# 1_power.net
KiCad netlist of a schematic drawn in Altium Designer
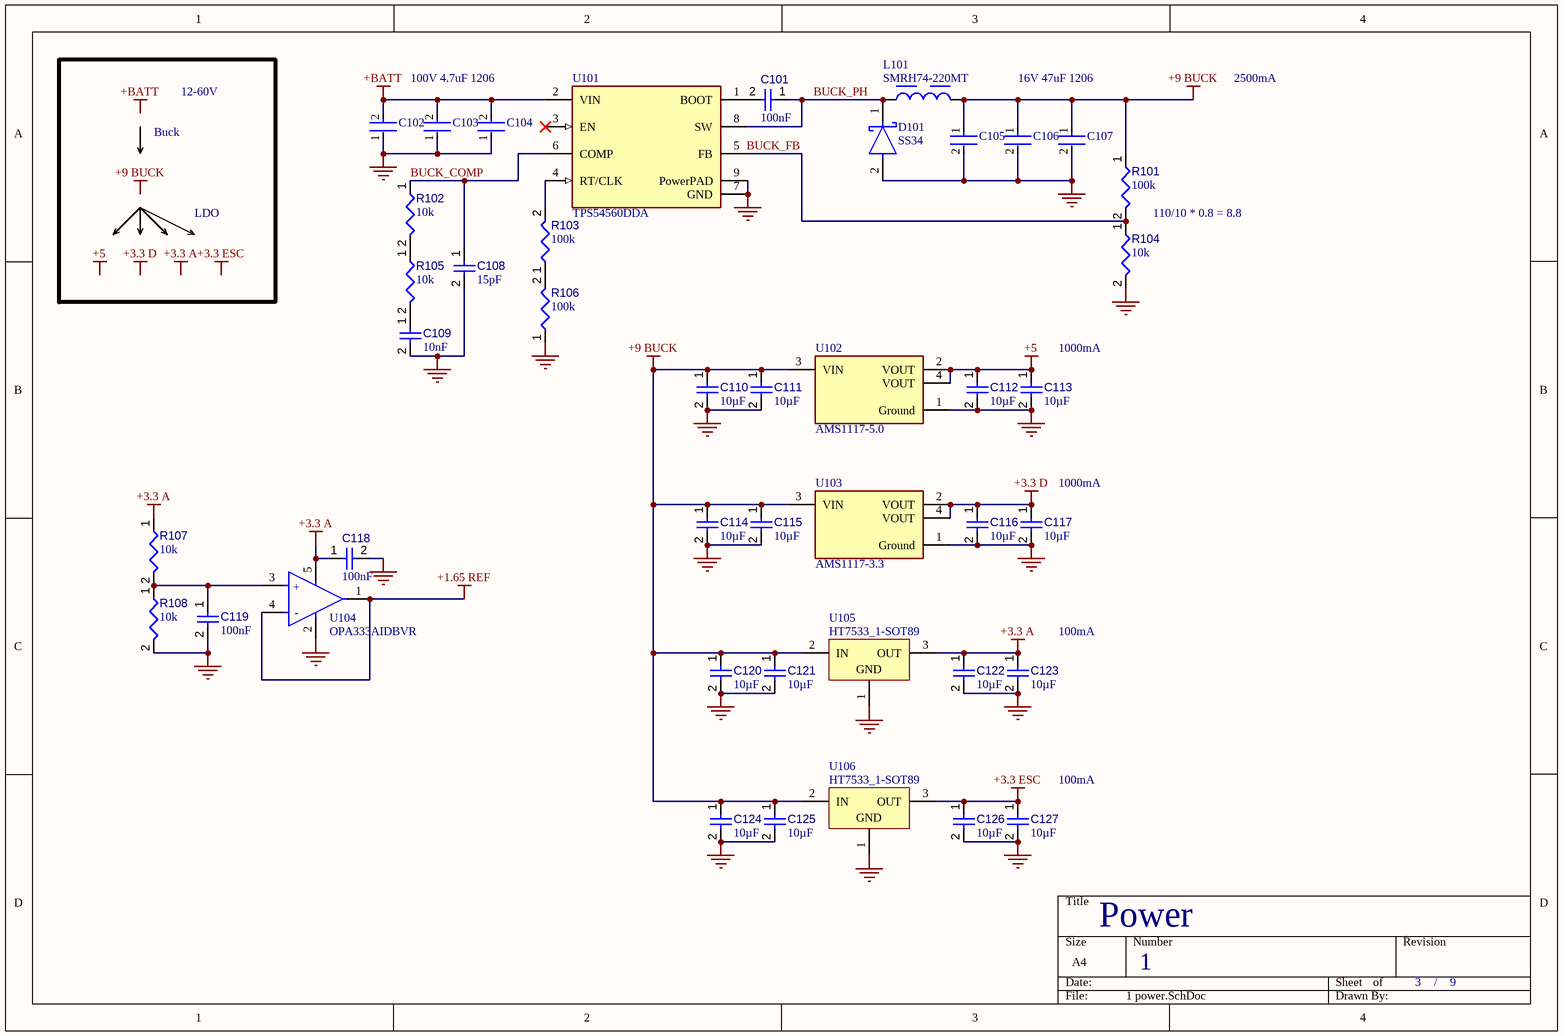
[diagram p0: 1 power.SchDoc]

(export (version "E")
  (design (tool "Eeschema 10.0.6"))
  (components
    (comp (ref "C101")
      (value "100nF")
      (footprint "CAPC0402(1005)60_L")
      (description "Chip Capacitor, 100nF +/-20%, 25V, 0402, Thickness 0.6 mm")
      (fields (field (name "TOLERANCE") "10%") (field (name "Comment") "Capacitor 100nF +/-20% 25V 0402"))
      (libsource (lib "UBC Uncrewed Aircraft Systems") (part "CAP-NP-2"))
    )
    (comp (ref "C102")
      (value "GRM31CZ72A475KE11L")
      (footprint "FP-GRM31C-0_3-e0_3_0_9-MFG")
      (description "Chip Multilayer Ceramic Capacitors for General Purpose, 1206, 4.7uF, X7R, 15%, 10%, 100V")
      (libsource (lib "Altium Content Vault") (part "f23184f103b6ebe33a8c269c53dcba6"))
    )
    (comp (ref "C103")
      (value "GRM31CZ72A475KE11L")
      (footprint "FP-GRM31C-0_3-e0_3_0_9-MFG")
      (description "Chip Multilayer Ceramic Capacitors for General Purpose, 1206, 4.7uF, X7R, 15%, 10%, 100V")
      (libsource (lib "Altium Content Vault") (part "f23184f103b6ebe33a8c269c53dcba6"))
    )
    (comp (ref "C104")
      (value "GRM31CZ72A475KE11L")
      (footprint "FP-GRM31C-0_3-e0_3_0_9-MFG")
      (description "Chip Multilayer Ceramic Capacitors for General Purpose, 1206, 4.7uF, X7R, 15%, 10%, 100V")
      (libsource (lib "Altium Content Vault") (part "f23184f103b6ebe33a8c269c53dcba6"))
    )
    (comp (ref "C105")
      (value "C3216X5R1C476M160AB")
      (footprint "FP-C3216-160-0_2-MFG")
      (description "Multilayer Ceramic Capacitors 47uF ±20% 16V X5R SMD 1206")
      (fields (field (name "TOLERANCE") "20%"))
      (libsource (lib "Altium Content Vault") (part "11868f565c42a9108669ba33697ecf6"))
    )
    (comp (ref "C106")
      (value "C3216X5R1C476M160AB")
      (footprint "FP-C3216-160-0_2-MFG")
      (description "Multilayer Ceramic Capacitors 47uF ±20% 16V X5R SMD 1206")
      (fields (field (name "TOLERANCE") "20%"))
      (libsource (lib "Altium Content Vault") (part "11868f565c42a9108669ba33697ecf6"))
    )
    (comp (ref "C107")
      (value "C3216X5R1C476M160AB")
      (footprint "FP-C3216-160-0_2-MFG")
      (description "Multilayer Ceramic Capacitors 47uF ±20% 16V X5R SMD 1206")
      (fields (field (name "TOLERANCE") "20%"))
      (libsource (lib "Altium Content Vault") (part "11868f565c42a9108669ba33697ecf6"))
    )
    (comp (ref "C108")
      (value "15pF")
      (footprint "CAPC0402(1005)60_L")
      (description "Chip Capacitor, 15pF +/-20%, 50V, 0402, Thickness 0.6 mm")
      (fields (field (name "TOLERANCE") "5%") (field (name "JLCPCB PART #") "C1548"))
      (libsource (lib "UBC Uncrewed Aircraft Systems") (part "CAP-NP-2"))
    )
    (comp (ref "C109")
      (value "10nF")
      (footprint "CAPC0402(1005)60_L")
      (description "Chip Capacitor, 10nF +/-20%, 50V, 0402, Thickness 0.6 mm")
      (fields (field (name "TOLERANCE") "5%") (field (name "JLCPCB PART #") "C15195"))
      (libsource (lib "UBC Uncrewed Aircraft Systems") (part "CAP-NP-2"))
    )
    (comp (ref "C110")
      (value "10µF")
      (footprint "CAPC0603(1608)100_L")
      (description "Chip Capacitor, 10µF +/-20%, 10V, 0603, Thickness 1 mm")
      (fields (field (name "TOLERANCE") "10%") (field (name "Comment") "Capacitor 10µF +/-20% 10V 0603"))
      (libsource (lib "UBC Uncrewed Aircraft Systems") (part "CAP-NP-2"))
    )
    (comp (ref "C111")
      (value "10µF")
      (footprint "CAPC0603(1608)100_L")
      (description "Chip Capacitor, 10µF +/-20%, 10V, 0603, Thickness 1 mm")
      (fields (field (name "TOLERANCE") "10%") (field (name "Comment") "Capacitor 10µF +/-20% 10V 0603"))
      (libsource (lib "UBC Uncrewed Aircraft Systems") (part "CAP-NP-2"))
    )
    (comp (ref "C112")
      (value "10µF")
      (footprint "CAPC0603(1608)100_L")
      (description "Chip Capacitor, 10µF +/-20%, 10V, 0603, Thickness 1 mm")
      (fields (field (name "TOLERANCE") "10%") (field (name "Comment") "Capacitor 10µF +/-20% 10V 0603"))
      (libsource (lib "UBC Uncrewed Aircraft Systems") (part "CAP-NP-2"))
    )
    (comp (ref "C113")
      (value "10µF")
      (footprint "CAPC0603(1608)100_L")
      (description "Chip Capacitor, 10µF +/-20%, 10V, 0603, Thickness 1 mm")
      (fields (field (name "TOLERANCE") "10%") (field (name "Comment") "Capacitor 10µF +/-20% 10V 0603"))
      (libsource (lib "UBC Uncrewed Aircraft Systems") (part "CAP-NP-2"))
    )
    (comp (ref "C114")
      (value "10µF")
      (footprint "CAPC0603(1608)100_L")
      (description "Chip Capacitor, 10µF +/-20%, 10V, 0603, Thickness 1 mm")
      (fields (field (name "TOLERANCE") "10%") (field (name "Comment") "Capacitor 10µF +/-20% 10V 0603"))
      (libsource (lib "UBC Uncrewed Aircraft Systems") (part "CAP-NP-2"))
    )
    (comp (ref "C115")
      (value "10µF")
      (footprint "CAPC0603(1608)100_L")
      (description "Chip Capacitor, 10µF +/-20%, 10V, 0603, Thickness 1 mm")
      (fields (field (name "TOLERANCE") "10%") (field (name "Comment") "Capacitor 10µF +/-20% 10V 0603"))
      (libsource (lib "UBC Uncrewed Aircraft Systems") (part "CAP-NP-2"))
    )
    (comp (ref "C116")
      (value "10µF")
      (footprint "CAPC0603(1608)100_L")
      (description "Chip Capacitor, 10µF +/-20%, 10V, 0603, Thickness 1 mm")
      (fields (field (name "TOLERANCE") "10%") (field (name "Comment") "Capacitor 10µF +/-20% 10V 0603"))
      (libsource (lib "UBC Uncrewed Aircraft Systems") (part "CAP-NP-2"))
    )
    (comp (ref "C117")
      (value "10µF")
      (footprint "CAPC0603(1608)100_L")
      (description "Chip Capacitor, 10µF +/-20%, 10V, 0603, Thickness 1 mm")
      (fields (field (name "TOLERANCE") "10%") (field (name "Comment") "Capacitor 10µF +/-20% 10V 0603"))
      (libsource (lib "UBC Uncrewed Aircraft Systems") (part "CAP-NP-2"))
    )
    (comp (ref "C118")
      (value "100nF")
      (footprint "CAPC0402(1005)60_L")
      (description "Chip Capacitor, 100nF +/-20%, 25V, 0402, Thickness 0.6 mm")
      (fields (field (name "TOLERANCE") "10%") (field (name "Comment") "Capacitor 100nF +/-20% 25V 0402"))
      (libsource (lib "UBC Uncrewed Aircraft Systems") (part "CAP-NP-2"))
    )
    (comp (ref "C119")
      (value "100nF")
      (footprint "CAPC0402(1005)60_L")
      (description "Chip Capacitor, 100nF +/-20%, 25V, 0402, Thickness 0.6 mm")
      (fields (field (name "TOLERANCE") "10%") (field (name "Comment") "Capacitor 100nF +/-20% 25V 0402"))
      (libsource (lib "UBC Uncrewed Aircraft Systems") (part "CAP-NP-2"))
    )
    (comp (ref "C120")
      (value "10µF")
      (footprint "CAPC0603(1608)100_L")
      (description "Chip Capacitor, 10µF +/-20%, 10V, 0603, Thickness 1 mm")
      (fields (field (name "TOLERANCE") "10%") (field (name "Comment") "Capacitor 10µF +/-20% 10V 0603"))
      (libsource (lib "UBC Uncrewed Aircraft Systems") (part "CAP-NP-2"))
    )
    (comp (ref "C121")
      (value "10µF")
      (footprint "CAPC0603(1608)100_L")
      (description "Chip Capacitor, 10µF +/-20%, 10V, 0603, Thickness 1 mm")
      (fields (field (name "TOLERANCE") "10%") (field (name "Comment") "Capacitor 10µF +/-20% 10V 0603"))
      (libsource (lib "UBC Uncrewed Aircraft Systems") (part "CAP-NP-2"))
    )
    (comp (ref "C122")
      (value "10µF")
      (footprint "CAPC0603(1608)100_L")
      (description "Chip Capacitor, 10µF +/-20%, 10V, 0603, Thickness 1 mm")
      (fields (field (name "TOLERANCE") "10%") (field (name "Comment") "Capacitor 10µF +/-20% 10V 0603"))
      (libsource (lib "UBC Uncrewed Aircraft Systems") (part "CAP-NP-2"))
    )
    (comp (ref "C123")
      (value "10µF")
      (footprint "CAPC0603(1608)100_L")
      (description "Chip Capacitor, 10µF +/-20%, 10V, 0603, Thickness 1 mm")
      (fields (field (name "TOLERANCE") "10%") (field (name "Comment") "Capacitor 10µF +/-20% 10V 0603"))
      (libsource (lib "UBC Uncrewed Aircraft Systems") (part "CAP-NP-2"))
    )
    (comp (ref "C124")
      (value "10µF")
      (footprint "CAPC0603(1608)100_L")
      (description "Chip Capacitor, 10µF +/-20%, 10V, 0603, Thickness 1 mm")
      (fields (field (name "TOLERANCE") "10%") (field (name "Comment") "Capacitor 10µF +/-20% 10V 0603"))
      (libsource (lib "UBC Uncrewed Aircraft Systems") (part "CAP-NP-2"))
    )
    (comp (ref "C125")
      (value "10µF")
      (footprint "CAPC0603(1608)100_L")
      (description "Chip Capacitor, 10µF +/-20%, 10V, 0603, Thickness 1 mm")
      (fields (field (name "TOLERANCE") "10%") (field (name "Comment") "Capacitor 10µF +/-20% 10V 0603"))
      (libsource (lib "UBC Uncrewed Aircraft Systems") (part "CAP-NP-2"))
    )
    (comp (ref "C126")
      (value "10µF")
      (footprint "CAPC0603(1608)100_L")
      (description "Chip Capacitor, 10µF +/-20%, 10V, 0603, Thickness 1 mm")
      (fields (field (name "TOLERANCE") "10%") (field (name "Comment") "Capacitor 10µF +/-20% 10V 0603"))
      (libsource (lib "UBC Uncrewed Aircraft Systems") (part "CAP-NP-2"))
    )
    (comp (ref "C127")
      (value "10µF")
      (footprint "CAPC0603(1608)100_L")
      (description "Chip Capacitor, 10µF +/-20%, 10V, 0603, Thickness 1 mm")
      (fields (field (name "TOLERANCE") "10%") (field (name "Comment") "Capacitor 10µF +/-20% 10V 0603"))
      (libsource (lib "UBC Uncrewed Aircraft Systems") (part "CAP-NP-2"))
    )
    (comp (ref "D101")
      (value "SS34")
      (footprint "FP-SMA-MFG")
      (description "DIODE SCHOTTKY 40V 3A SMA")
      (fields (field (name "VOLTAGE") "40V"))
      (libsource (lib "Altium Content Vault") (part "1d6ec82d83fb6aee721767c19dac4b9"))
    )
    (comp (ref "L101")
      (value "SMRH74-220MT")
      (footprint "WE-HCI_7040")
      (fields (field (name "TOLERANCE") "20%"))
      (libsource (lib "Altium Content Vault") (part "Inductor - 3"))
    )
    (comp (ref "R101")
      (value "100k")
      (footprint "RESC0402(1005)_L")
      (description "Chip Resistor, 100 kOhms, +/-1 %, 63 mW, -55 to 155 degC, 0402")
      (fields (field (name "TOLERANCE") "1%") (field (name "POWER") "63mW"))
      (libsource (lib "UBC Uncrewed Aircraft Systems") (part "RES-2"))
    )
    (comp (ref "R102")
      (value "10k")
      (footprint "RESC0402(1005)_L")
      (description "Chip Resistor, 10 kOhms, +/-1 %, 63 mW, -55 to 125 degC, 0402")
      (fields (field (name "POWER") "63mW") (field (name "TOLERANCE") "1%"))
      (libsource (lib "UBC Uncrewed Aircraft Systems") (part "RES-2"))
    )
    (comp (ref "R103")
      (value "100k")
      (footprint "RESC0402(1005)_L")
      (description "Chip Resistor, 100 kOhms, +/-1 %, 63 mW, -55 to 155 degC, 0402")
      (fields (field (name "TOLERANCE") "1%") (field (name "POWER") "63mW"))
      (libsource (lib "UBC Uncrewed Aircraft Systems") (part "RES-2"))
    )
    (comp (ref "R104")
      (value "10k")
      (footprint "RESC0402(1005)_L")
      (description "Chip Resistor, 10 kOhms, +/-1 %, 63 mW, -55 to 125 degC, 0402")
      (fields (field (name "POWER") "63mW") (field (name "TOLERANCE") "1%"))
      (libsource (lib "UBC Uncrewed Aircraft Systems") (part "RES-2"))
    )
    (comp (ref "R105")
      (value "10k")
      (footprint "RESC0402(1005)_L")
      (description "Chip Resistor, 10 kOhms, +/-1 %, 63 mW, -55 to 125 degC, 0402")
      (fields (field (name "POWER") "63mW") (field (name "TOLERANCE") "1%"))
      (libsource (lib "UBC Uncrewed Aircraft Systems") (part "RES-2"))
    )
    (comp (ref "R106")
      (value "100k")
      (footprint "RESC0402(1005)_L")
      (description "Chip Resistor, 100 kOhms, +/-1 %, 63 mW, -55 to 155 degC, 0402")
      (fields (field (name "TOLERANCE") "1%") (field (name "POWER") "63mW"))
      (libsource (lib "UBC Uncrewed Aircraft Systems") (part "RES-2"))
    )
    (comp (ref "R107")
      (value "10k")
      (footprint "RESC0402(1005)_L")
      (description "Chip Resistor, 10 kOhms, +/-1 %, 63 mW, -55 to 125 degC, 0402")
      (fields (field (name "POWER") "63mW") (field (name "TOLERANCE") "1%"))
      (libsource (lib "UBC Uncrewed Aircraft Systems") (part "RES-2"))
    )
    (comp (ref "R108")
      (value "10k")
      (footprint "RESC0402(1005)_L")
      (description "Chip Resistor, 10 kOhms, +/-1 %, 63 mW, -55 to 125 degC, 0402")
      (fields (field (name "POWER") "63mW") (field (name "TOLERANCE") "1%"))
      (libsource (lib "UBC Uncrewed Aircraft Systems") (part "RES-2"))
    )
    (comp (ref "U101")
      (value "TPS54560DDA")
      (footprint "FP-DDA0008E-IPC_C")
      (description "IC REG BCK SPLIT RAIL ADJ 8SOPWR")
      (fields
        (field (name "OCTOPART") "https://octopart.com/tps54560dda-texas+instruments-26977150")
        (field (name "MANUFACTURER") "Texas Instruments")
      )
      (libsource (lib "Altium Content Vault") (part "92fa32c5fb0b456cc3a934f0e7b6d8f"))
    )
    (comp (ref "U102")
      (value "AMS1117-5.0")
      (footprint "FP-AMS1117-IPC_C")
      (description "LDO Voltage Regulators 1A, 5.0V")
      (fields
        (field (name "MANUFACTURER") "Advanced Monolithic Systems")
        (field (name "JLCPCB PART #") "C6187")
      )
      (libsource (lib "Altium Content Vault") (part "8bdbb5f8e77002000e30dd2845d0354"))
    )
    (comp (ref "U103")
      (value "AMS1117-3.3")
      (footprint "FP-AMS1117-IPC_C")
      (description "LDO Voltage Regulators 1A, 3.3V")
      (fields
        (field (name "OCTOPART") "https://octopart.com/ams1117-3.3-advanced+monolithic+systems-25899300")
        (field (name "MANUFACTURER") "Advanced Monolithic Systems")
      )
      (libsource (lib "Altium Content Vault") (part "8bdbb5f8e77002000e30dd2845d0354"))
    )
    (comp (ref "U104")
      (value "OPA333AIDBVR")
      (footprint "FP-DBV0005A-MFG")
      (description "IC OPAMP ZER-DRIFT 1CIRC SOT23-5")
      (libsource (lib "Altium Content Vault") (part "1dcd28e651784f0a5a8ed6f8452eeff"))
    )
    (comp (ref "U105")
      (value "HT7533_1-SOT89")
      (footprint "SOT89_L")
      (description "100mA Low Power LDO, Output Voltage 3.3V, SOT89 Pkg")
      (libsource (lib "Altium Content Vault") (part "PM-REG-HT75xx-1-IL3"))
    )
    (comp (ref "U106")
      (value "HT7533_1-SOT89")
      (footprint "SOT89_L")
      (description "100mA Low Power LDO, Output Voltage 3.3V, SOT89 Pkg")
      (libsource (lib "Altium Content Vault") (part "PM-REG-HT75xx-1-IL3"))
    )
  )
  (nets
    (net (code "1") (name "+1.65 REF") (class "Default")
      (node (ref "U104") (pin "1") (pinfunction "OUT_1") (pintype "passive"))
      (node (ref "U104") (pin "4") (pinfunction "-IN_4") (pintype "tri_state"))
    )
    (net (code "2") (name "+3.3 A") (class "Default")
      (node (ref "C118") (pin "1") (pinfunction "1_1") (pintype "passive"))
      (node (ref "C122") (pin "1") (pinfunction "1_1") (pintype "passive"))
      (node (ref "C123") (pin "1") (pinfunction "1_1") (pintype "passive"))
      (node (ref "R107") (pin "1") (pinfunction "1_1") (pintype "passive"))
      (node (ref "U104") (pin "5") (pinfunction "V+_5") (pintype "power_in"))
      (node (ref "U105") (pin "3") (pinfunction "OUT_3") (pintype "power_in"))
    )
    (net (code "3") (name "+3.3 D") (class "Default")
      (node (ref "C116") (pin "1") (pinfunction "1_1") (pintype "passive"))
      (node (ref "C117") (pin "1") (pinfunction "1_1") (pintype "passive"))
      (node (ref "U103") (pin "2") (pinfunction "VOUT_2") (pintype "passive"))
      (node (ref "U103") (pin "4") (pinfunction "VOUT_4") (pintype "passive"))
    )
    (net (code "4") (name "+3.3 ESC") (class "Default")
      (node (ref "C126") (pin "1") (pinfunction "1_1") (pintype "passive"))
      (node (ref "C127") (pin "1") (pinfunction "1_1") (pintype "passive"))
      (node (ref "U106") (pin "3") (pinfunction "OUT_3") (pintype "power_in"))
    )
    (net (code "5") (name "+5") (class "Default")
      (node (ref "C112") (pin "1") (pinfunction "1_1") (pintype "passive"))
      (node (ref "C113") (pin "1") (pinfunction "1_1") (pintype "passive"))
      (node (ref "U102") (pin "2") (pinfunction "VOUT_2") (pintype "passive"))
      (node (ref "U102") (pin "4") (pinfunction "VOUT_4") (pintype "passive"))
    )
    (net (code "6") (name "+9 BUCK") (class "Default")
      (node (ref "C105") (pin "1") (pinfunction "1_1") (pintype "passive"))
      (node (ref "C106") (pin "1") (pinfunction "1_1") (pintype "passive"))
      (node (ref "C107") (pin "1") (pinfunction "1_1") (pintype "passive"))
      (node (ref "C110") (pin "1") (pinfunction "1_1") (pintype "passive"))
      (node (ref "C111") (pin "1") (pinfunction "1_1") (pintype "passive"))
      (node (ref "C114") (pin "1") (pinfunction "1_1") (pintype "passive"))
      (node (ref "C115") (pin "1") (pinfunction "1_1") (pintype "passive"))
      (node (ref "C120") (pin "1") (pinfunction "1_1") (pintype "passive"))
      (node (ref "C121") (pin "1") (pinfunction "1_1") (pintype "passive"))
      (node (ref "C124") (pin "1") (pinfunction "1_1") (pintype "passive"))
      (node (ref "C125") (pin "1") (pinfunction "1_1") (pintype "passive"))
      (node (ref "L101") (pin "2") (pinfunction "2_2") (pintype "passive"))
      (node (ref "R101") (pin "1") (pinfunction "1_1") (pintype "passive"))
      (node (ref "U102") (pin "3") (pinfunction "VIN_3") (pintype "power_in"))
      (node (ref "U103") (pin "3") (pinfunction "VIN_3") (pintype "power_in"))
      (node (ref "U105") (pin "2") (pinfunction "IN_2") (pintype "power_in"))
      (node (ref "U106") (pin "2") (pinfunction "IN_2") (pintype "power_in"))
    )
    (net (code "7") (name "+BATT") (class "Default")
      (node (ref "C102") (pin "2") (pinfunction "2_2") (pintype "passive"))
      (node (ref "C103") (pin "2") (pinfunction "2_2") (pintype "passive"))
      (node (ref "C104") (pin "2") (pinfunction "2_2") (pintype "passive"))
      (node (ref "U101") (pin "2") (pinfunction "VIN_2") (pintype "power_in"))
    )
    (net (code "8") (name "/BUCK_COMP") (class "Default")
      (node (ref "C108") (pin "1") (pinfunction "1_1") (pintype "passive"))
      (node (ref "R102") (pin "1") (pinfunction "1_1") (pintype "passive"))
      (node (ref "U101") (pin "6") (pinfunction "COMP_6") (pintype "passive"))
    )
    (net (code "9") (name "/BUCK_FB") (class "Default")
      (node (ref "R101") (pin "2") (pinfunction "2_2") (pintype "passive"))
      (node (ref "R104") (pin "1") (pinfunction "1_1") (pintype "passive"))
      (node (ref "U101") (pin "5") (pinfunction "FB_5") (pintype "passive"))
    )
    (net (code "10") (name "/BUCK_PH") (class "Default")
      (node (ref "C101") (pin "1") (pinfunction "1_1") (pintype "passive"))
      (node (ref "D101") (pin "1") (pinfunction "C_1") (pintype "passive"))
      (node (ref "L101") (pin "1") (pinfunction "1_1") (pintype "passive"))
      (node (ref "U101") (pin "8") (pinfunction "SW_8") (pintype "passive"))
    )
    (net (code "11") (name "GND") (class "Default")
      (node (ref "C102") (pin "1") (pinfunction "1_1") (pintype "passive"))
      (node (ref "C103") (pin "1") (pinfunction "1_1") (pintype "passive"))
      (node (ref "C104") (pin "1") (pinfunction "1_1") (pintype "passive"))
      (node (ref "C105") (pin "2") (pinfunction "2_2") (pintype "passive"))
      (node (ref "C106") (pin "2") (pinfunction "2_2") (pintype "passive"))
      (node (ref "C107") (pin "2") (pinfunction "2_2") (pintype "passive"))
      (node (ref "C108") (pin "2") (pinfunction "2_2") (pintype "passive"))
      (node (ref "C109") (pin "2") (pinfunction "2_2") (pintype "passive"))
      (node (ref "C110") (pin "2") (pinfunction "2_2") (pintype "passive"))
      (node (ref "C111") (pin "2") (pinfunction "2_2") (pintype "passive"))
      (node (ref "C112") (pin "2") (pinfunction "2_2") (pintype "passive"))
      (node (ref "C113") (pin "2") (pinfunction "2_2") (pintype "passive"))
      (node (ref "C114") (pin "2") (pinfunction "2_2") (pintype "passive"))
      (node (ref "C115") (pin "2") (pinfunction "2_2") (pintype "passive"))
      (node (ref "C116") (pin "2") (pinfunction "2_2") (pintype "passive"))
      (node (ref "C117") (pin "2") (pinfunction "2_2") (pintype "passive"))
      (node (ref "C118") (pin "2") (pinfunction "2_2") (pintype "passive"))
      (node (ref "C119") (pin "2") (pinfunction "2_2") (pintype "passive"))
      (node (ref "C120") (pin "2") (pinfunction "2_2") (pintype "passive"))
      (node (ref "C121") (pin "2") (pinfunction "2_2") (pintype "passive"))
      (node (ref "C122") (pin "2") (pinfunction "2_2") (pintype "passive"))
      (node (ref "C123") (pin "2") (pinfunction "2_2") (pintype "passive"))
      (node (ref "C124") (pin "2") (pinfunction "2_2") (pintype "passive"))
      (node (ref "C125") (pin "2") (pinfunction "2_2") (pintype "passive"))
      (node (ref "C126") (pin "2") (pinfunction "2_2") (pintype "passive"))
      (node (ref "C127") (pin "2") (pinfunction "2_2") (pintype "passive"))
      (node (ref "D101") (pin "2") (pinfunction "A_2") (pintype "passive"))
      (node (ref "R104") (pin "2") (pinfunction "2_2") (pintype "passive"))
      (node (ref "R106") (pin "1") (pinfunction "1_1") (pintype "passive"))
      (node (ref "R108") (pin "2") (pinfunction "2_2") (pintype "passive"))
      (node (ref "U101") (pin "7") (pinfunction "GND_7") (pintype "power_in"))
      (node (ref "U101") (pin "9") (pinfunction "PowerPAD_9") (pintype "power_in"))
      (node (ref "U102") (pin "1") (pinfunction "Ground_1") (pintype "power_in"))
      (node (ref "U103") (pin "1") (pinfunction "Ground_1") (pintype "power_in"))
      (node (ref "U104") (pin "2") (pinfunction "V-_2") (pintype "power_in"))
      (node (ref "U105") (pin "1") (pinfunction "GND_1") (pintype "power_in"))
      (node (ref "U106") (pin "1") (pinfunction "GND_1") (pintype "power_in"))
    )
    (net (code "12") (name "Net-(C109-Pad1)") (class "Default")
      (node (ref "C109") (pin "1") (pinfunction "1_1") (pintype "passive"))
      (node (ref "R105") (pin "2") (pinfunction "2_2") (pintype "passive"))
    )
    (net (code "13") (name "Net-(R102-Pad2)") (class "Default")
      (node (ref "R102") (pin "2") (pinfunction "2_2") (pintype "passive"))
      (node (ref "R105") (pin "1") (pinfunction "1_1") (pintype "passive"))
    )
    (net (code "14") (name "Net-(R103-Pad1)") (class "Default")
      (node (ref "R103") (pin "1") (pinfunction "1_1") (pintype "passive"))
      (node (ref "R106") (pin "2") (pinfunction "2_2") (pintype "passive"))
    )
    (net (code "15") (name "Net-(U101-BOOT)") (class "Default")
      (node (ref "C101") (pin "2") (pinfunction "2_2") (pintype "passive"))
      (node (ref "U101") (pin "1") (pinfunction "BOOT_1") (pintype "passive"))
    )
    (net (code "16") (name "Net-(U101-RT{slash}CLK)") (class "Default")
      (node (ref "R103") (pin "2") (pinfunction "2_2") (pintype "passive"))
      (node (ref "U101") (pin "4") (pinfunction "RT/CLK_4") (pintype "input"))
    )
    (net (code "17") (name "Net-(U104-+IN)") (class "Default")
      (node (ref "C119") (pin "1") (pinfunction "1_1") (pintype "passive"))
      (node (ref "R107") (pin "2") (pinfunction "2_2") (pintype "passive"))
      (node (ref "R108") (pin "1") (pinfunction "1_1") (pintype "passive"))
      (node (ref "U104") (pin "3") (pinfunction "+IN_3") (pintype "tri_state"))
    )
    (net (code "18") (name "unconnected-(U101-EN-Pad3)") (class "Default")
      (node (ref "U101") (pin "3") (pinfunction "EN_3") (pintype "input+no_connect"))
    )
  )
)
